# KS2E_DumbFanController.net
KiCad netlist of a schematic drawn in Altium Designer
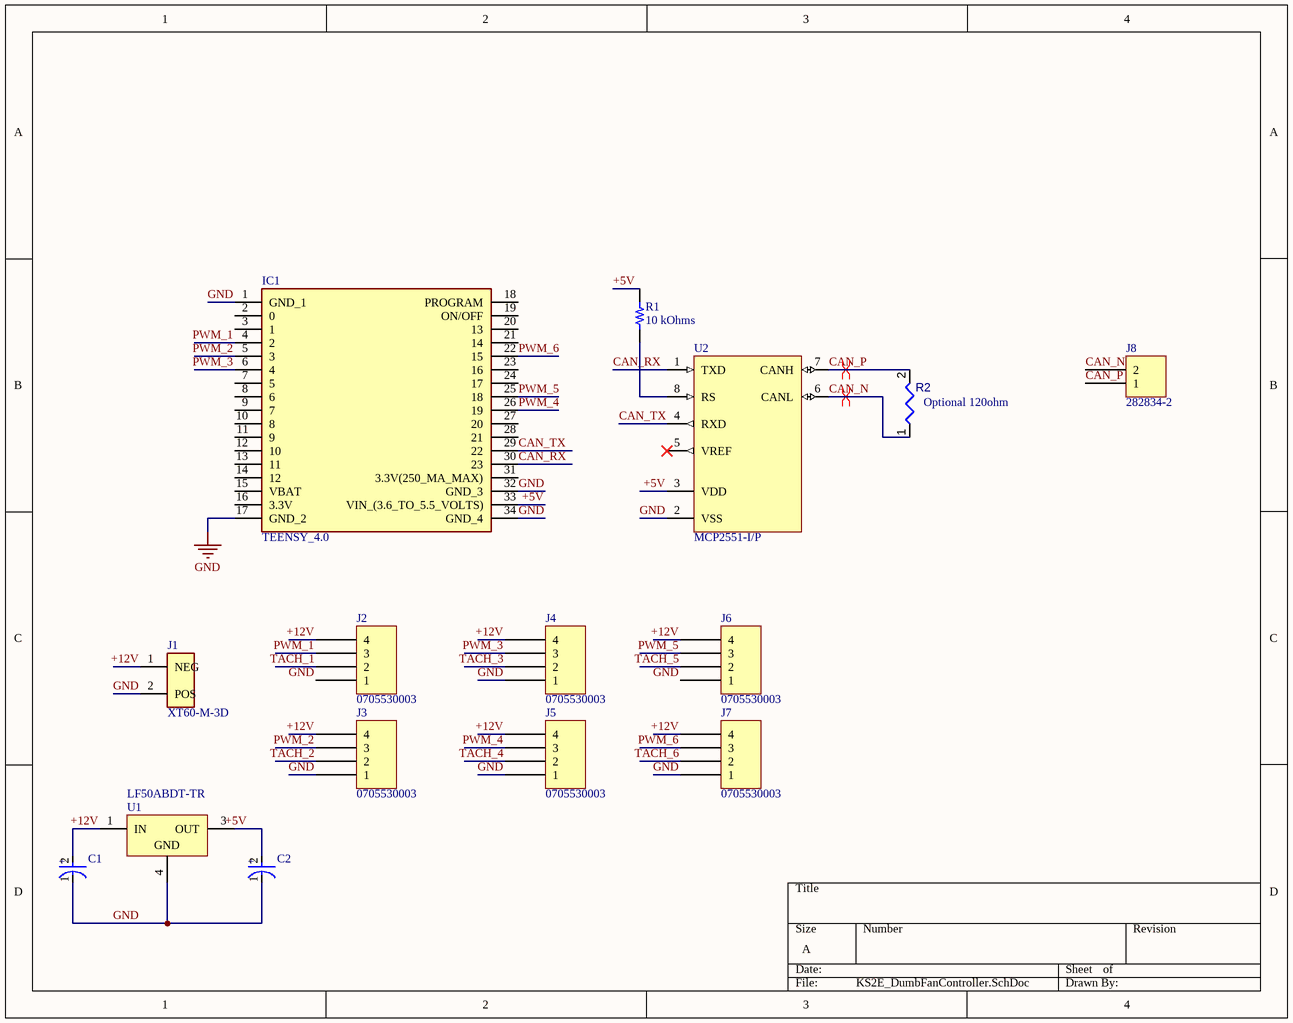
[diagram p0: KS2E_DumbFanController.SchDoc]

(export (version "E")
  (design (tool "Eeschema 10.0.6"))
  (components
    (comp (ref "C1")
      (value "EEEFK1E100R")
      (footprint "FP-FKB-MFG")
      (description "CAP ALUM 10UF 20% 25V SMD")
      (fields (field (name "VOLTAGE") "25V") (field (name "TOLERANCE") "20%"))
      (libsource (lib "Altium Content Vault") (part "203bc49f2ac43e59fd269a8c329ed05"))
    )
    (comp (ref "C2")
      (value "EEEFK1E100R")
      (footprint "FP-FKB-MFG")
      (description "CAP ALUM 10UF 20% 25V SMD")
      (fields (field (name "VOLTAGE") "25V") (field (name "TOLERANCE") "20%"))
      (libsource (lib "Altium Content Vault") (part "203bc49f2ac43e59fd269a8c329ed05"))
    )
    (comp (ref "IC1")
      (value "TEENSY_4.0")
      (footprint "SamacSys:TEENSY40")
      (description "Integrated Circuit")
      (fields (field (name "MANUFACTURER_PART_NUMBER") "TEENSY 4.0"))
      (libsource (lib "*") (part "TEENSY_4.0"))
    )
    (comp (ref "J1")
      (value "XT60-M-3D")
      (footprint "AMASS_XT60-M")
      (description "Plug; DC supply; XT60; male; PIN: 2; for cable; soldered; 30A; 500V")
      (fields (field (name "MP") "XT60-M") (field (name "MF") "AMASS"))
      (libsource (lib "XT60-M-3D") (part "XT60-M-3D"))
    )
    (comp (ref "J2")
      (value "0705530003")
      (footprint "MOLEX SDA-70553-4PIN")
      (description "CONN HEADER R/A 4POS 2.54MM")
      (fields (field (name "MANUFACTURER") "Molex"))
      (libsource (lib "Celestial Altium Library - altium_library") (part "4 Pin"))
    )
    (comp (ref "J3")
      (value "0705530003")
      (footprint "MOLEX SDA-70553-4PIN")
      (description "CONN HEADER R/A 4POS 2.54MM")
      (fields (field (name "MANUFACTURER") "Molex"))
      (libsource (lib "Celestial Altium Library - altium_library") (part "4 Pin"))
    )
    (comp (ref "J4")
      (value "0705530003")
      (footprint "MOLEX SDA-70553-4PIN")
      (description "CONN HEADER R/A 4POS 2.54MM")
      (fields (field (name "MANUFACTURER") "Molex"))
      (libsource (lib "Celestial Altium Library - altium_library") (part "4 Pin"))
    )
    (comp (ref "J5")
      (value "0705530003")
      (footprint "MOLEX SDA-70553-4PIN")
      (description "CONN HEADER R/A 4POS 2.54MM")
      (fields (field (name "MANUFACTURER") "Molex"))
      (libsource (lib "Celestial Altium Library - altium_library") (part "4 Pin"))
    )
    (comp (ref "J6")
      (value "0705530003")
      (footprint "MOLEX SDA-70553-4PIN")
      (description "CONN HEADER R/A 4POS 2.54MM")
      (fields (field (name "MANUFACTURER") "Molex"))
      (libsource (lib "Celestial Altium Library - altium_library") (part "4 Pin"))
    )
    (comp (ref "J7")
      (value "0705530003")
      (footprint "MOLEX SDA-70553-4PIN")
      (description "CONN HEADER R/A 4POS 2.54MM")
      (fields (field (name "MANUFACTURER") "Molex"))
      (libsource (lib "Celestial Altium Library - altium_library") (part "4 Pin"))
    )
    (comp (ref "J8")
      (value "282834-2")
      (footprint "TE 282834-2")
      (description "TERM BLK 2P SIDE ENT 2.54MM PCB")
      (fields (field (name "MANUFACTURER") "TE Connectivity AMP Connectors") (field (name "VOLTAGE") "150V"))
      (libsource (lib "Celestial Altium Library - altium_library") (part "2 Pin"))
    )
    (comp (ref "R1")
      (value "10 kOhms")
      (footprint "RES 1206_3216")
      (description "RES SMD 10K OHM 1% 1/4W 1206")
      (fields
        (field (name "PART NUMBER") "CRG1206F10K")
        (field (name "MANUFACTURER") "TE Connectivity Passive Product")
      )
      (libsource (lib "Celestial Altium Library - altium_library") (part "Resistor"))
    )
    (comp (ref "R2")
      (value "Jumper 0603")
      (footprint "RESC0603(1608)_L")
      (libsource (lib "Kennesaw Motorsports") (part "RES-2"))
    )
    (comp (ref "U1")
      (value "LF50ABDT-TR")
      (footprint "TO-252_M")
      (description "500mA, Very Low Drop (0.45V) Voltage Regulator, 5V, 3-Pin DPAK, Tape and Reel")
      (libsource (lib "Altium Content Vault") (part "PM-REG-L4940-SOT3"))
    )
    (comp (ref "U2")
      (value "MCP2551-I/P")
      (footprint "PDIP300-P8")
      (description "High-Speed CAN Transceiver, 8-Pin PDIP, Industrial Temperature")
      (libsource (lib "Altium Content Vault") (part "COM-TRX-MCP2551-8"))
    )
  )
  (nets
    (net (code "1") (name "/+5V") (class "Default")
      (node (ref "C2") (pin "2") (pinfunction "A_2") (pintype "passive"))
      (node (ref "IC1") (pin "33") (pinfunction "VIN_(3.6_TO_5.5_VOLTS)_33") (pintype "passive"))
      (node (ref "R1") (pin "2") (pinfunction "2_2") (pintype "passive"))
      (node (ref "U1") (pin "3") (pinfunction "OUT_3") (pintype "power_in"))
      (node (ref "U2") (pin "3") (pinfunction "VDD_3") (pintype "power_in"))
    )
    (net (code "2") (name "/+12V") (class "Default")
      (node (ref "C1") (pin "2") (pinfunction "A_2") (pintype "passive"))
      (node (ref "J1") (pin "1") (pinfunction "NEG_1") (pintype "passive"))
      (node (ref "J2") (pin "4") (pinfunction "4_4") (pintype "passive"))
      (node (ref "J3") (pin "4") (pinfunction "4_4") (pintype "passive"))
      (node (ref "J4") (pin "4") (pinfunction "4_4") (pintype "passive"))
      (node (ref "J5") (pin "4") (pinfunction "4_4") (pintype "passive"))
      (node (ref "J6") (pin "4") (pinfunction "4_4") (pintype "passive"))
      (node (ref "J7") (pin "4") (pinfunction "4_4") (pintype "passive"))
      (node (ref "U1") (pin "1") (pinfunction "IN_1") (pintype "power_in"))
    )
    (net (code "3") (name "/CAN_N") (class "Default")
      (node (ref "J8") (pin "2") (pinfunction "2_2") (pintype "passive"))
      (node (ref "R2") (pin "1") (pinfunction "1_1") (pintype "passive"))
      (node (ref "U2") (pin "6") (pinfunction "CANL_6") (pintype "bidirectional"))
    )
    (net (code "4") (name "/CAN_P") (class "Default")
      (node (ref "J8") (pin "1") (pinfunction "1_1") (pintype "passive"))
      (node (ref "R2") (pin "2") (pinfunction "2_2") (pintype "passive"))
      (node (ref "U2") (pin "7") (pinfunction "CANH_7") (pintype "bidirectional"))
    )
    (net (code "5") (name "/CAN_RX") (class "Default")
      (node (ref "IC1") (pin "30") (pinfunction "23_30") (pintype "passive"))
      (node (ref "U2") (pin "1") (pinfunction "TXD_1") (pintype "input"))
    )
    (net (code "6") (name "/CAN_TX") (class "Default")
      (node (ref "IC1") (pin "29") (pinfunction "22_29") (pintype "passive"))
      (node (ref "U2") (pin "4") (pinfunction "RXD_4") (pintype "output"))
    )
    (net (code "7") (name "/PWM_1") (class "Default")
      (node (ref "IC1") (pin "4") (pinfunction "2_4") (pintype "passive"))
      (node (ref "J2") (pin "3") (pinfunction "3_3") (pintype "passive"))
    )
    (net (code "8") (name "/PWM_2") (class "Default")
      (node (ref "IC1") (pin "5") (pinfunction "3_5") (pintype "passive"))
      (node (ref "J3") (pin "3") (pinfunction "3_3") (pintype "passive"))
    )
    (net (code "9") (name "/PWM_3") (class "Default")
      (node (ref "IC1") (pin "6") (pinfunction "4_6") (pintype "passive"))
      (node (ref "J4") (pin "3") (pinfunction "3_3") (pintype "passive"))
    )
    (net (code "10") (name "/PWM_4") (class "Default")
      (node (ref "IC1") (pin "26") (pinfunction "19_26") (pintype "passive"))
      (node (ref "J5") (pin "3") (pinfunction "3_3") (pintype "passive"))
    )
    (net (code "11") (name "/PWM_5") (class "Default")
      (node (ref "IC1") (pin "25") (pinfunction "18_25") (pintype "passive"))
      (node (ref "J6") (pin "3") (pinfunction "3_3") (pintype "passive"))
    )
    (net (code "12") (name "/PWM_6") (class "Default")
      (node (ref "IC1") (pin "22") (pinfunction "15_22") (pintype "passive"))
      (node (ref "J7") (pin "3") (pinfunction "3_3") (pintype "passive"))
    )
    (net (code "13") (name "/TACH_1") (class "Default")
      (node (ref "J2") (pin "2") (pinfunction "2_2") (pintype "passive"))
    )
    (net (code "14") (name "/TACH_2") (class "Default")
      (node (ref "J3") (pin "2") (pinfunction "2_2") (pintype "passive"))
    )
    (net (code "15") (name "/TACH_3") (class "Default")
      (node (ref "J4") (pin "2") (pinfunction "2_2") (pintype "passive"))
    )
    (net (code "16") (name "/TACH_4") (class "Default")
      (node (ref "J5") (pin "2") (pinfunction "2_2") (pintype "passive"))
    )
    (net (code "17") (name "/TACH_5") (class "Default")
      (node (ref "J6") (pin "2") (pinfunction "2_2") (pintype "passive"))
    )
    (net (code "18") (name "/TACH_6") (class "Default")
      (node (ref "J7") (pin "2") (pinfunction "2_2") (pintype "passive"))
    )
    (net (code "19") (name "GND") (class "Default")
      (node (ref "C1") (pin "1") (pinfunction "C_1") (pintype "passive"))
      (node (ref "C2") (pin "1") (pinfunction "C_1") (pintype "passive"))
      (node (ref "IC1") (pin "1") (pinfunction "GND_1_1") (pintype "passive"))
      (node (ref "IC1") (pin "17") (pinfunction "GND_2_17") (pintype "passive"))
      (node (ref "IC1") (pin "32") (pinfunction "GND_3_32") (pintype "passive"))
      (node (ref "IC1") (pin "34") (pinfunction "GND_4_34") (pintype "passive"))
      (node (ref "J1") (pin "2") (pinfunction "POS_2") (pintype "passive"))
      (node (ref "J2") (pin "1") (pinfunction "1_1") (pintype "passive"))
      (node (ref "J3") (pin "1") (pinfunction "1_1") (pintype "passive"))
      (node (ref "J4") (pin "1") (pinfunction "1_1") (pintype "passive"))
      (node (ref "J5") (pin "1") (pinfunction "1_1") (pintype "passive"))
      (node (ref "J6") (pin "1") (pinfunction "1_1") (pintype "passive"))
      (node (ref "J7") (pin "1") (pinfunction "1_1") (pintype "passive"))
      (node (ref "U1") (pin "4") (pinfunction "GND_4") (pintype "power_in"))
      (node (ref "U2") (pin "2") (pinfunction "VSS_2") (pintype "power_in"))
    )
    (net (code "20") (name "Net-(U2-RS)") (class "Default")
      (node (ref "R1") (pin "1") (pinfunction "1_1") (pintype "passive"))
      (node (ref "U2") (pin "8") (pinfunction "RS_8") (pintype "input"))
    )
    (net (code "21") (name "unconnected-(IC1-0-Pad2)") (class "Default")
      (node (ref "IC1") (pin "2") (pinfunction "0_2") (pintype "passive"))
    )
    (net (code "22") (name "unconnected-(IC1-1-Pad3)") (class "Default")
      (node (ref "IC1") (pin "3") (pinfunction "1_3") (pintype "passive"))
    )
    (net (code "23") (name "unconnected-(IC1-3.3V(250_MA_MAX)-Pad31)") (class "Default")
      (node (ref "IC1") (pin "31") (pinfunction "3.3V(250_MA_MAX)_31") (pintype "passive"))
    )
    (net (code "24") (name "unconnected-(IC1-3.3V-Pad16)") (class "Default")
      (node (ref "IC1") (pin "16") (pinfunction "3.3V_16") (pintype "passive"))
    )
    (net (code "25") (name "unconnected-(IC1-5-Pad7)") (class "Default")
      (node (ref "IC1") (pin "7") (pinfunction "5_7") (pintype "passive"))
    )
    (net (code "26") (name "unconnected-(IC1-6-Pad8)") (class "Default")
      (node (ref "IC1") (pin "8") (pinfunction "6_8") (pintype "passive"))
    )
    (net (code "27") (name "unconnected-(IC1-7-Pad9)") (class "Default")
      (node (ref "IC1") (pin "9") (pinfunction "7_9") (pintype "passive"))
    )
    (net (code "28") (name "unconnected-(IC1-8-Pad10)") (class "Default")
      (node (ref "IC1") (pin "10") (pinfunction "8_10") (pintype "passive"))
    )
    (net (code "29") (name "unconnected-(IC1-9-Pad11)") (class "Default")
      (node (ref "IC1") (pin "11") (pinfunction "9_11") (pintype "passive"))
    )
    (net (code "30") (name "unconnected-(IC1-10-Pad12)") (class "Default")
      (node (ref "IC1") (pin "12") (pinfunction "10_12") (pintype "passive"))
    )
    (net (code "31") (name "unconnected-(IC1-11-Pad13)") (class "Default")
      (node (ref "IC1") (pin "13") (pinfunction "11_13") (pintype "passive"))
    )
    (net (code "32") (name "unconnected-(IC1-12-Pad14)") (class "Default")
      (node (ref "IC1") (pin "14") (pinfunction "12_14") (pintype "passive"))
    )
    (net (code "33") (name "unconnected-(IC1-13-Pad20)") (class "Default")
      (node (ref "IC1") (pin "20") (pinfunction "13_20") (pintype "passive"))
    )
    (net (code "34") (name "unconnected-(IC1-14-Pad21)") (class "Default")
      (node (ref "IC1") (pin "21") (pinfunction "14_21") (pintype "passive"))
    )
    (net (code "35") (name "unconnected-(IC1-16-Pad23)") (class "Default")
      (node (ref "IC1") (pin "23") (pinfunction "16_23") (pintype "passive"))
    )
    (net (code "36") (name "unconnected-(IC1-17-Pad24)") (class "Default")
      (node (ref "IC1") (pin "24") (pinfunction "17_24") (pintype "passive"))
    )
    (net (code "37") (name "unconnected-(IC1-20-Pad27)") (class "Default")
      (node (ref "IC1") (pin "27") (pinfunction "20_27") (pintype "passive"))
    )
    (net (code "38") (name "unconnected-(IC1-21-Pad28)") (class "Default")
      (node (ref "IC1") (pin "28") (pinfunction "21_28") (pintype "passive"))
    )
    (net (code "39") (name "unconnected-(IC1-ON{slash}OFF-Pad19)") (class "Default")
      (node (ref "IC1") (pin "19") (pinfunction "ON/OFF_19") (pintype "passive"))
    )
    (net (code "40") (name "unconnected-(IC1-PROGRAM-Pad18)") (class "Default")
      (node (ref "IC1") (pin "18") (pinfunction "PROGRAM_18") (pintype "passive"))
    )
    (net (code "41") (name "unconnected-(IC1-VBAT-Pad15)") (class "Default")
      (node (ref "IC1") (pin "15") (pinfunction "VBAT_15") (pintype "passive"))
    )
    (net (code "42") (name "unconnected-(U2-VREF-Pad5)") (class "Default")
      (node (ref "U2") (pin "5") (pinfunction "VREF_5") (pintype "output+no_connect"))
    )
  )
)
